# CONNECTOR_B.net
KiCad netlist of a schematic drawn in Altium Designer
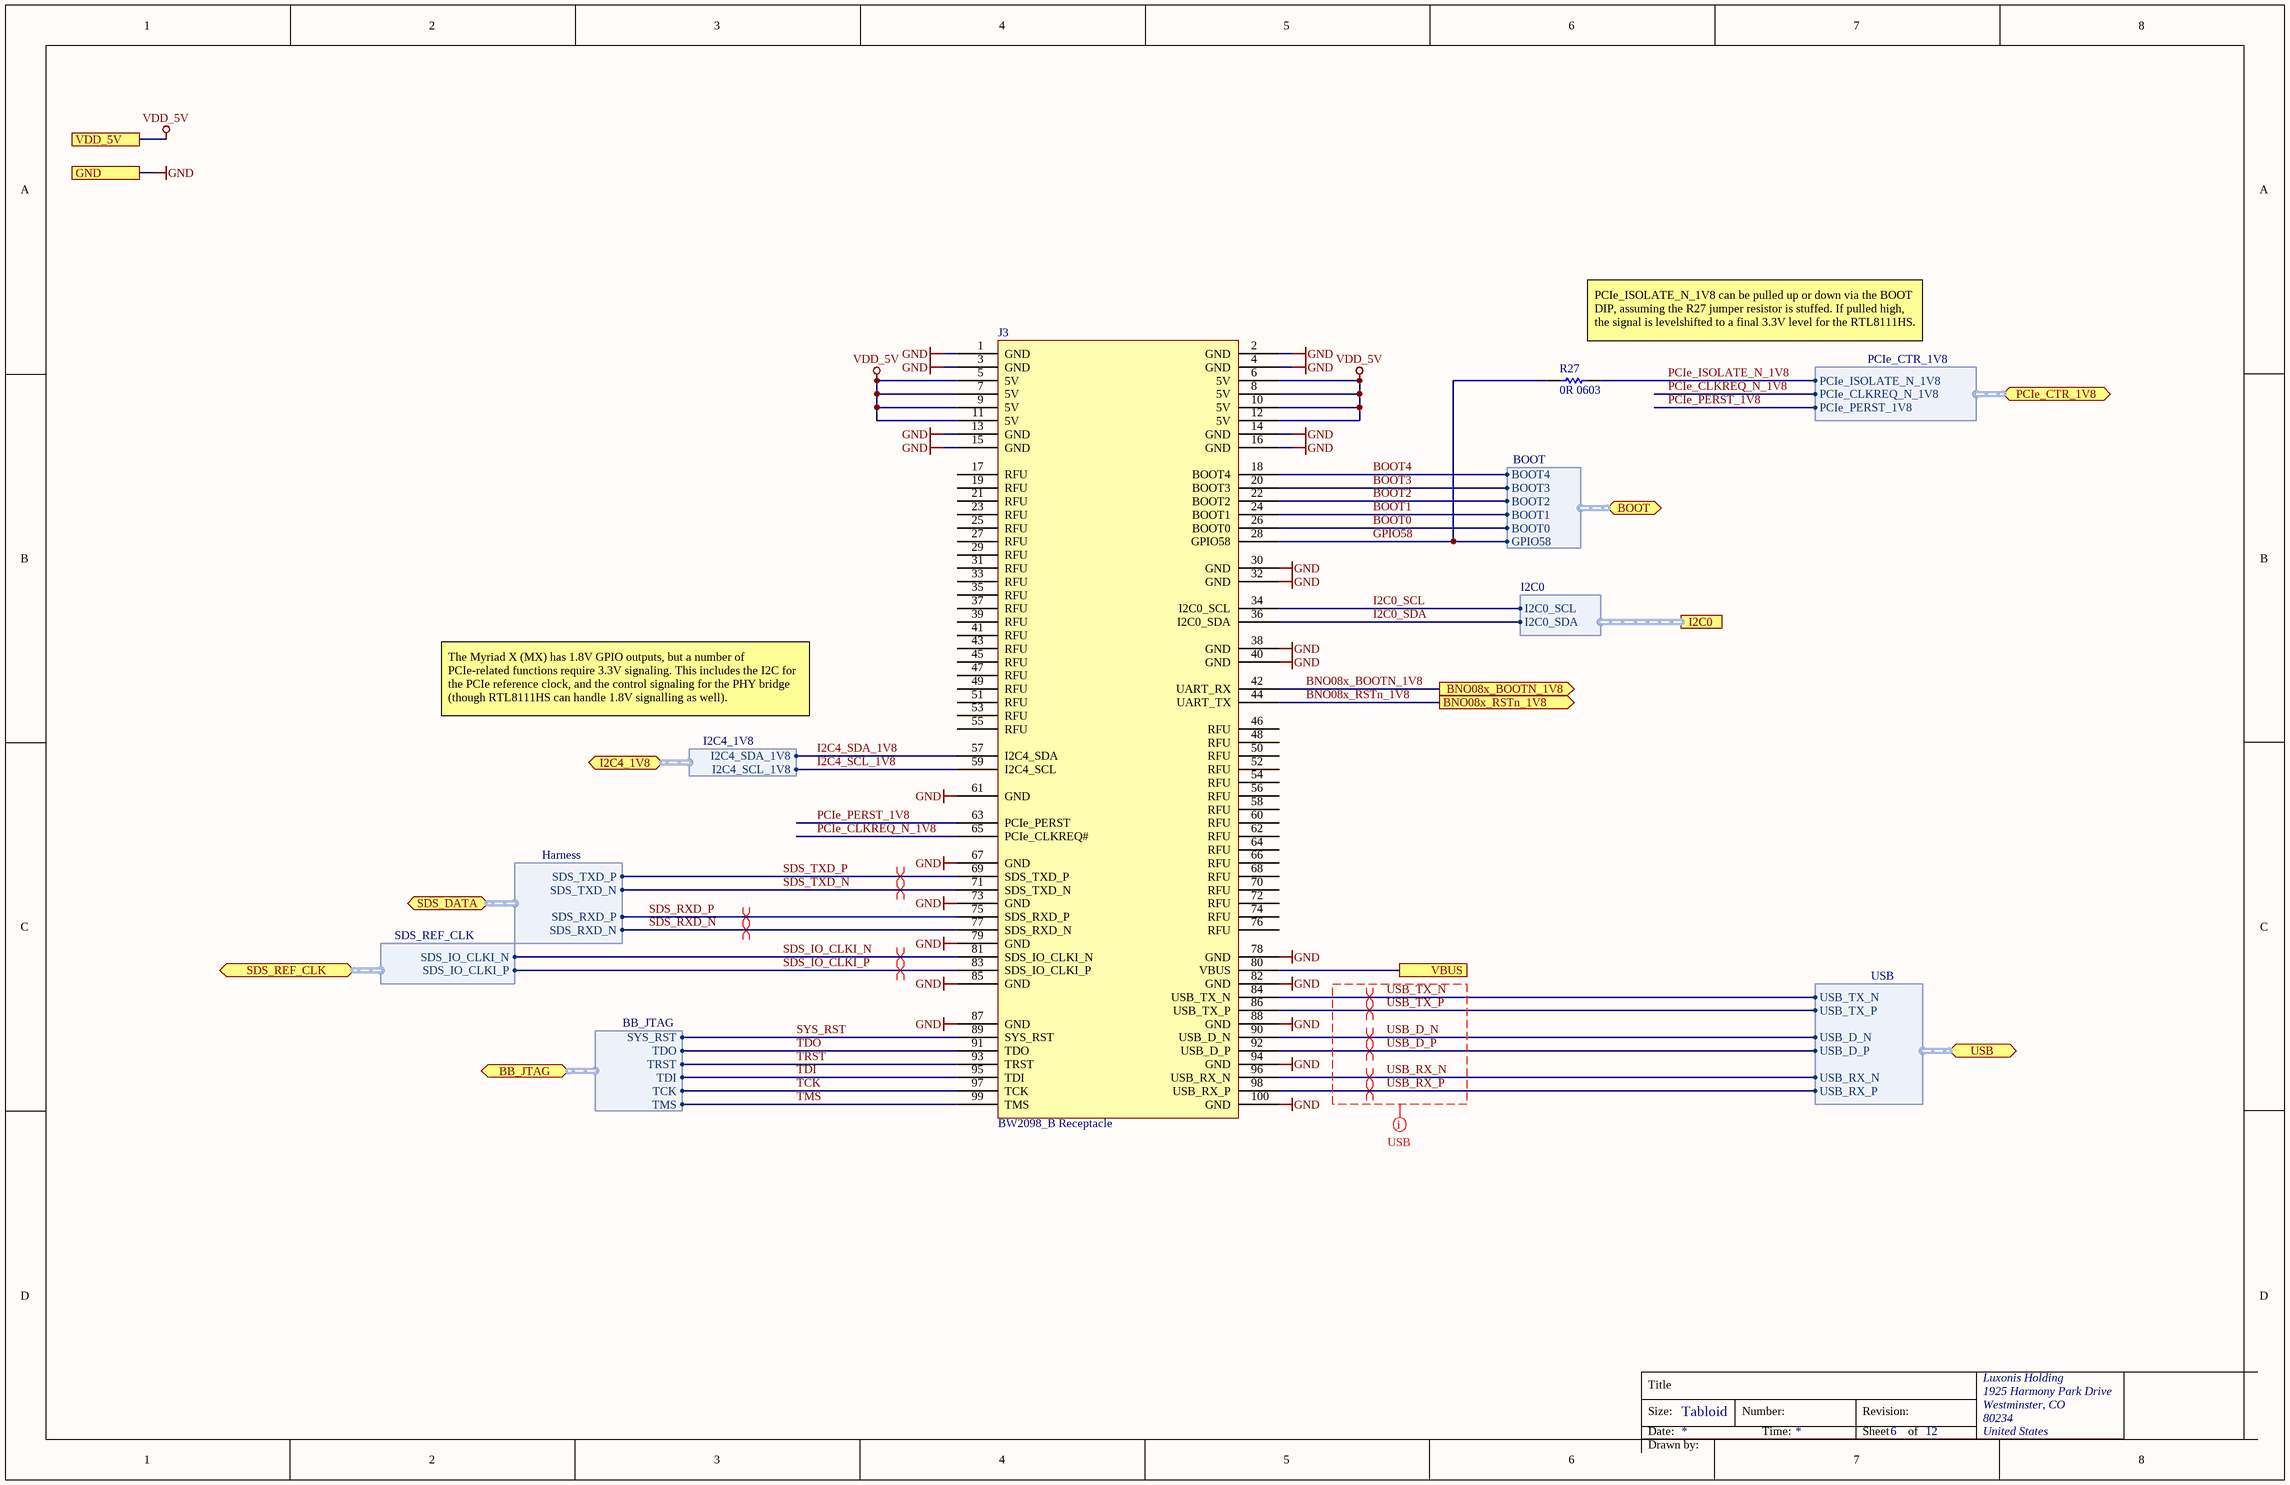
[diagram p0: CONNECTOR_B.SchDoc]

(export (version "E")
  (design (tool "Eeschema 10.0.6"))
  (components
    (comp (ref "J3")
      (value "BW2098_B Receptacle")
      (footprint "LuxonisMaster:DF40HC-3.0-100DS-0.4V_minpad")
      (description "CONN RCPT 100POS 0.4MM SMD GOLD BW2098_B Receptacle")
      (libsource (lib "BW2098POE") (part "DF40HC(3.0)-100DS-0.4V_BW2098_B"))
    )
    (comp (ref "R27")
      (value "0R 0603")
      (footprint "RES_Altium_Vault_Generic:RESC0603(1608)_N")
      (fields (field (name "TOLERANCE") "5%"))
      (libsource (lib "LuxonisMaster") (part "CRCW06030000Z0EA"))
    )
  )
  (nets
    (net (code "9") (name "/BNO08x_BOOTN_1V8") (class "Default")
      (node (ref "J3") (pin "42") (pinfunction "UART_RX_42") (pintype "passive"))
    )
    (net (code "10") (name "/BNO08x_RSTn_1V8") (class "Default")
      (node (ref "J3") (pin "44") (pinfunction "UART_TX_44") (pintype "passive"))
    )
    (net (code "11") (name "/BOOT0") (class "Default")
      (node (ref "J3") (pin "26") (pinfunction "BOOT0_26") (pintype "passive"))
    )
    (net (code "12") (name "/BOOT1") (class "Default")
      (node (ref "J3") (pin "24") (pinfunction "BOOT1_24") (pintype "passive"))
    )
    (net (code "13") (name "/BOOT2") (class "Default")
      (node (ref "J3") (pin "22") (pinfunction "BOOT2_22") (pintype "passive"))
    )
    (net (code "14") (name "/BOOT3") (class "Default")
      (node (ref "J3") (pin "20") (pinfunction "BOOT3_20") (pintype "passive"))
    )
    (net (code "15") (name "/BOOT4") (class "Default")
      (node (ref "J3") (pin "18") (pinfunction "BOOT4_18") (pintype "passive"))
    )
    (net (code "16") (name "/GPIO58") (class "Default")
      (node (ref "J3") (pin "28") (pinfunction "GPIO58_28") (pintype "passive"))
      (node (ref "R27") (pin "1") (pinfunction "1_1") (pintype "passive"))
    )
    (net (code "17") (name "/I2C0_SCL") (class "Default")
      (node (ref "J3") (pin "34") (pinfunction "I2C0_SCL_34") (pintype "passive"))
    )
    (net (code "18") (name "/I2C0_SDA") (class "Default")
      (node (ref "J3") (pin "36") (pinfunction "I2C0_SDA_36") (pintype "passive"))
    )
    (net (code "19") (name "/I2C4_SCL_1V8") (class "Default")
      (node (ref "J3") (pin "59") (pinfunction "I2C4_SCL_59") (pintype "passive"))
    )
    (net (code "20") (name "/I2C4_SDA_1V8") (class "Default")
      (node (ref "J3") (pin "57") (pinfunction "I2C4_SDA_57") (pintype "passive"))
    )
    (net (code "21") (name "/PCIe_CLKREQ_N_1V8") (class "Default")
      (node (ref "J3") (pin "65") (pinfunction "PCIe_CLKREQ#_65") (pintype "passive"))
    )
    (net (code "22") (name "/PCIe_ISOLATE_N_1V8") (class "Default")
      (node (ref "R27") (pin "2") (pinfunction "2_2") (pintype "passive"))
    )
    (net (code "23") (name "/PCIe_PERST_1V8") (class "Default")
      (node (ref "J3") (pin "63") (pinfunction "PCIe_PERST_63") (pintype "passive"))
    )
    (net (code "24") (name "/SDS_IO_CLKI_N") (class "Default")
      (node (ref "J3") (pin "81") (pinfunction "SDS_IO_CLKI_N_81") (pintype "passive"))
    )
    (net (code "25") (name "/SDS_IO_CLKI_P") (class "Default")
      (node (ref "J3") (pin "83") (pinfunction "SDS_IO_CLKI_P_83") (pintype "passive"))
    )
    (net (code "26") (name "/SDS_RXD_N") (class "Default")
      (node (ref "J3") (pin "77") (pinfunction "SDS_RXD_N_77") (pintype "passive"))
    )
    (net (code "27") (name "/SDS_RXD_P") (class "Default")
      (node (ref "J3") (pin "75") (pinfunction "SDS_RXD_P_75") (pintype "passive"))
    )
    (net (code "28") (name "/SDS_TXD_N") (class "Default")
      (node (ref "J3") (pin "71") (pinfunction "SDS_TXD_N_71") (pintype "passive"))
    )
    (net (code "29") (name "/SDS_TXD_P") (class "Default")
      (node (ref "J3") (pin "69") (pinfunction "SDS_TXD_P_69") (pintype "passive"))
    )
    (net (code "30") (name "/SYS_RST") (class "Default")
      (node (ref "J3") (pin "89") (pinfunction "SYS_RST_89") (pintype "passive"))
    )
    (net (code "31") (name "/TCK") (class "Default")
      (node (ref "J3") (pin "97") (pinfunction "TCK_97") (pintype "passive"))
    )
    (net (code "32") (name "/TDI") (class "Default")
      (node (ref "J3") (pin "95") (pinfunction "TDI_95") (pintype "passive"))
    )
    (net (code "33") (name "/TDO") (class "Default")
      (node (ref "J3") (pin "91") (pinfunction "TDO_91") (pintype "passive"))
    )
    (net (code "34") (name "/TMS") (class "Default")
      (node (ref "J3") (pin "99") (pinfunction "TMS_99") (pintype "passive"))
    )
    (net (code "35") (name "/TRST") (class "Default")
      (node (ref "J3") (pin "93") (pinfunction "TRST_93") (pintype "passive"))
    )
    (net (code "36") (name "/USB_D_N") (class "Default")
      (node (ref "J3") (pin "90") (pinfunction "USB_D_N_90") (pintype "passive"))
    )
    (net (code "37") (name "/USB_D_P") (class "Default")
      (node (ref "J3") (pin "92") (pinfunction "USB_D_P_92") (pintype "passive"))
    )
    (net (code "38") (name "/USB_RX_N") (class "Default")
      (node (ref "J3") (pin "96") (pinfunction "USB_RX_N_96") (pintype "passive"))
    )
    (net (code "39") (name "/USB_RX_P") (class "Default")
      (node (ref "J3") (pin "98") (pinfunction "USB_RX_P_98") (pintype "passive"))
    )
    (net (code "40") (name "/USB_TX_N") (class "Default")
      (node (ref "J3") (pin "84") (pinfunction "USB_TX_N_84") (pintype "passive"))
    )
    (net (code "41") (name "/USB_TX_P") (class "Default")
      (node (ref "J3") (pin "86") (pinfunction "USB_TX_P_86") (pintype "passive"))
    )
    (net (code "42") (name "/VBUS") (class "Default")
      (node (ref "J3") (pin "80") (pinfunction "VBUS_80") (pintype "passive"))
    )
    (net (code "51") (name "GND") (class "Default")
      (node (ref "J3") (pin "1") (pinfunction "GND_1") (pintype "passive"))
      (node (ref "J3") (pin "100") (pinfunction "GND_100") (pintype "passive"))
      (node (ref "J3") (pin "13") (pinfunction "GND_13") (pintype "passive"))
      (node (ref "J3") (pin "14") (pinfunction "GND_14") (pintype "passive"))
      (node (ref "J3") (pin "15") (pinfunction "GND_15") (pintype "passive"))
      (node (ref "J3") (pin "16") (pinfunction "GND_16") (pintype "passive"))
      (node (ref "J3") (pin "2") (pinfunction "GND_2") (pintype "passive"))
      (node (ref "J3") (pin "3") (pinfunction "GND_3") (pintype "passive"))
      (node (ref "J3") (pin "30") (pinfunction "GND_30") (pintype "passive"))
      (node (ref "J3") (pin "32") (pinfunction "GND_32") (pintype "passive"))
      (node (ref "J3") (pin "38") (pinfunction "GND_38") (pintype "passive"))
      (node (ref "J3") (pin "4") (pinfunction "GND_4") (pintype "passive"))
      (node (ref "J3") (pin "40") (pinfunction "GND_40") (pintype "passive"))
      (node (ref "J3") (pin "61") (pinfunction "GND_61") (pintype "passive"))
      (node (ref "J3") (pin "67") (pinfunction "GND_67") (pintype "passive"))
      (node (ref "J3") (pin "73") (pinfunction "GND_73") (pintype "passive"))
      (node (ref "J3") (pin "78") (pinfunction "GND_78") (pintype "passive"))
      (node (ref "J3") (pin "79") (pinfunction "GND_79") (pintype "passive"))
      (node (ref "J3") (pin "82") (pinfunction "GND_82") (pintype "passive"))
      (node (ref "J3") (pin "85") (pinfunction "GND_85") (pintype "passive"))
      (node (ref "J3") (pin "87") (pinfunction "GND_87") (pintype "passive"))
      (node (ref "J3") (pin "88") (pinfunction "GND_88") (pintype "passive"))
      (node (ref "J3") (pin "94") (pinfunction "GND_94") (pintype "passive"))
    )
    (net (code "52") (name "VDD_5V") (class "Default")
      (node (ref "J3") (pin "10") (pinfunction "5V_10") (pintype "passive"))
      (node (ref "J3") (pin "11") (pinfunction "5V_11") (pintype "passive"))
      (node (ref "J3") (pin "12") (pinfunction "5V_12") (pintype "passive"))
      (node (ref "J3") (pin "5") (pinfunction "5V_5") (pintype "passive"))
      (node (ref "J3") (pin "6") (pinfunction "5V_6") (pintype "passive"))
      (node (ref "J3") (pin "7") (pinfunction "5V_7") (pintype "passive"))
      (node (ref "J3") (pin "8") (pinfunction "5V_8") (pintype "passive"))
      (node (ref "J3") (pin "9") (pinfunction "5V_9") (pintype "passive"))
    )
    (net (code "53") (name "unconnected-(J3-RFU-Pad17)") (class "Default")
      (node (ref "J3") (pin "17") (pinfunction "RFU_17") (pintype "passive"))
    )
    (net (code "54") (name "unconnected-(J3-RFU-Pad19)") (class "Default")
      (node (ref "J3") (pin "19") (pinfunction "RFU_19") (pintype "passive"))
    )
    (net (code "55") (name "unconnected-(J3-RFU-Pad21)") (class "Default")
      (node (ref "J3") (pin "21") (pinfunction "RFU_21") (pintype "passive"))
    )
    (net (code "56") (name "unconnected-(J3-RFU-Pad23)") (class "Default")
      (node (ref "J3") (pin "23") (pinfunction "RFU_23") (pintype "passive"))
    )
    (net (code "57") (name "unconnected-(J3-RFU-Pad25)") (class "Default")
      (node (ref "J3") (pin "25") (pinfunction "RFU_25") (pintype "passive"))
    )
    (net (code "58") (name "unconnected-(J3-RFU-Pad27)") (class "Default")
      (node (ref "J3") (pin "27") (pinfunction "RFU_27") (pintype "passive"))
    )
    (net (code "59") (name "unconnected-(J3-RFU-Pad29)") (class "Default")
      (node (ref "J3") (pin "29") (pinfunction "RFU_29") (pintype "passive"))
    )
    (net (code "60") (name "unconnected-(J3-RFU-Pad31)") (class "Default")
      (node (ref "J3") (pin "31") (pinfunction "RFU_31") (pintype "passive"))
    )
    (net (code "61") (name "unconnected-(J3-RFU-Pad33)") (class "Default")
      (node (ref "J3") (pin "33") (pinfunction "RFU_33") (pintype "passive"))
    )
    (net (code "62") (name "unconnected-(J3-RFU-Pad35)") (class "Default")
      (node (ref "J3") (pin "35") (pinfunction "RFU_35") (pintype "passive"))
    )
    (net (code "63") (name "unconnected-(J3-RFU-Pad37)") (class "Default")
      (node (ref "J3") (pin "37") (pinfunction "RFU_37") (pintype "passive"))
    )
    (net (code "64") (name "unconnected-(J3-RFU-Pad39)") (class "Default")
      (node (ref "J3") (pin "39") (pinfunction "RFU_39") (pintype "passive"))
    )
    (net (code "65") (name "unconnected-(J3-RFU-Pad41)") (class "Default")
      (node (ref "J3") (pin "41") (pinfunction "RFU_41") (pintype "passive"))
    )
    (net (code "66") (name "unconnected-(J3-RFU-Pad43)") (class "Default")
      (node (ref "J3") (pin "43") (pinfunction "RFU_43") (pintype "passive"))
    )
    (net (code "67") (name "unconnected-(J3-RFU-Pad45)") (class "Default")
      (node (ref "J3") (pin "45") (pinfunction "RFU_45") (pintype "passive"))
    )
    (net (code "68") (name "unconnected-(J3-RFU-Pad46)") (class "Default")
      (node (ref "J3") (pin "46") (pinfunction "RFU_46") (pintype "passive"))
    )
    (net (code "69") (name "unconnected-(J3-RFU-Pad47)") (class "Default")
      (node (ref "J3") (pin "47") (pinfunction "RFU_47") (pintype "passive"))
    )
    (net (code "70") (name "unconnected-(J3-RFU-Pad48)") (class "Default")
      (node (ref "J3") (pin "48") (pinfunction "RFU_48") (pintype "passive"))
    )
    (net (code "71") (name "unconnected-(J3-RFU-Pad49)") (class "Default")
      (node (ref "J3") (pin "49") (pinfunction "RFU_49") (pintype "passive"))
    )
    (net (code "72") (name "unconnected-(J3-RFU-Pad50)") (class "Default")
      (node (ref "J3") (pin "50") (pinfunction "RFU_50") (pintype "passive"))
    )
    (net (code "73") (name "unconnected-(J3-RFU-Pad51)") (class "Default")
      (node (ref "J3") (pin "51") (pinfunction "RFU_51") (pintype "passive"))
    )
    (net (code "74") (name "unconnected-(J3-RFU-Pad52)") (class "Default")
      (node (ref "J3") (pin "52") (pinfunction "RFU_52") (pintype "passive"))
    )
    (net (code "75") (name "unconnected-(J3-RFU-Pad53)") (class "Default")
      (node (ref "J3") (pin "53") (pinfunction "RFU_53") (pintype "passive"))
    )
    (net (code "76") (name "unconnected-(J3-RFU-Pad54)") (class "Default")
      (node (ref "J3") (pin "54") (pinfunction "RFU_54") (pintype "passive"))
    )
    (net (code "77") (name "unconnected-(J3-RFU-Pad55)") (class "Default")
      (node (ref "J3") (pin "55") (pinfunction "RFU_55") (pintype "passive"))
    )
    (net (code "78") (name "unconnected-(J3-RFU-Pad56)") (class "Default")
      (node (ref "J3") (pin "56") (pinfunction "RFU_56") (pintype "passive"))
    )
    (net (code "79") (name "unconnected-(J3-RFU-Pad58)") (class "Default")
      (node (ref "J3") (pin "58") (pinfunction "RFU_58") (pintype "passive"))
    )
    (net (code "80") (name "unconnected-(J3-RFU-Pad60)") (class "Default")
      (node (ref "J3") (pin "60") (pinfunction "RFU_60") (pintype "passive"))
    )
    (net (code "81") (name "unconnected-(J3-RFU-Pad62)") (class "Default")
      (node (ref "J3") (pin "62") (pinfunction "RFU_62") (pintype "passive"))
    )
    (net (code "82") (name "unconnected-(J3-RFU-Pad64)") (class "Default")
      (node (ref "J3") (pin "64") (pinfunction "RFU_64") (pintype "passive"))
    )
    (net (code "83") (name "unconnected-(J3-RFU-Pad66)") (class "Default")
      (node (ref "J3") (pin "66") (pinfunction "RFU_66") (pintype "passive"))
    )
    (net (code "84") (name "unconnected-(J3-RFU-Pad68)") (class "Default")
      (node (ref "J3") (pin "68") (pinfunction "RFU_68") (pintype "passive"))
    )
    (net (code "85") (name "unconnected-(J3-RFU-Pad70)") (class "Default")
      (node (ref "J3") (pin "70") (pinfunction "RFU_70") (pintype "passive"))
    )
    (net (code "86") (name "unconnected-(J3-RFU-Pad72)") (class "Default")
      (node (ref "J3") (pin "72") (pinfunction "RFU_72") (pintype "passive"))
    )
    (net (code "87") (name "unconnected-(J3-RFU-Pad74)") (class "Default")
      (node (ref "J3") (pin "74") (pinfunction "RFU_74") (pintype "passive"))
    )
    (net (code "88") (name "unconnected-(J3-RFU-Pad76)") (class "Default")
      (node (ref "J3") (pin "76") (pinfunction "RFU_76") (pintype "passive"))
    )
  )
)
